# flyback_diode.net
KiCad netlist of a schematic drawn in EAGLE
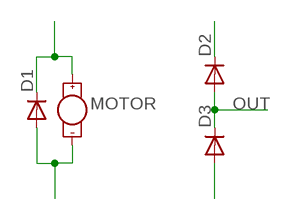
[diagram p0: schematic, sheet 1]

(export (version "E")
  (design (tool "Eeschema 10.0.6"))
  (components
    (comp (ref "D1")
      (value "DIODE1N4148")
      (footprint "eagle-import:DIODE-1N4148")
      (libsource (lib "eagle-import") (part "DIODE1N4148"))
    )
    (comp (ref "D2")
      (value "DIODE1N4148")
      (footprint "eagle-import:DIODE-1N4148")
      (libsource (lib "eagle-import") (part "DIODE1N4148"))
    )
    (comp (ref "D3")
      (value "DIODE1N4148")
      (footprint "eagle-import:DIODE-1N4148")
      (libsource (lib "eagle-import") (part "DIODE1N4148"))
    )
    (comp (ref "MOTOR")
      (value "MOTOR10MM")
      (footprint "eagle-import:VIBE-MOTOR-10MM")
      (libsource (lib "eagle-import") (part "MOTOR10MM"))
    )
  )
  (nets
    (net (code "1") (name "/OUT") (class "Default")
      (node (ref "D2") (pin "A") (pinfunction "A_A") (pintype "passive"))
      (node (ref "D3") (pin "C") (pinfunction "C_C") (pintype "passive"))
    )
    (net (code "2") (name "Net-(D1-PadA)") (class "Default")
      (node (ref "D1") (pin "A") (pinfunction "A_A") (pintype "passive"))
      (node (ref "MOTOR") (pin "-") (pinfunction "-_-") (pintype "bidirectional"))
    )
    (net (code "3") (name "Net-(D1-PadC)") (class "Default")
      (node (ref "D1") (pin "C") (pinfunction "C_C") (pintype "passive"))
      (node (ref "MOTOR") (pin "+") (pinfunction "+_+") (pintype "bidirectional"))
    )
    (net (code "4") (name "unconnected-(D2-PadC)") (class "Default")
      (node (ref "D2") (pin "C") (pinfunction "C_C") (pintype "passive"))
    )
    (net (code "5") (name "unconnected-(D3-PadA)") (class "Default")
      (node (ref "D3") (pin "A") (pinfunction "A_A") (pintype "passive"))
    )
  )
)
